# PIC32MZ.net
KiCad netlist of a schematic drawn in Altium Designer
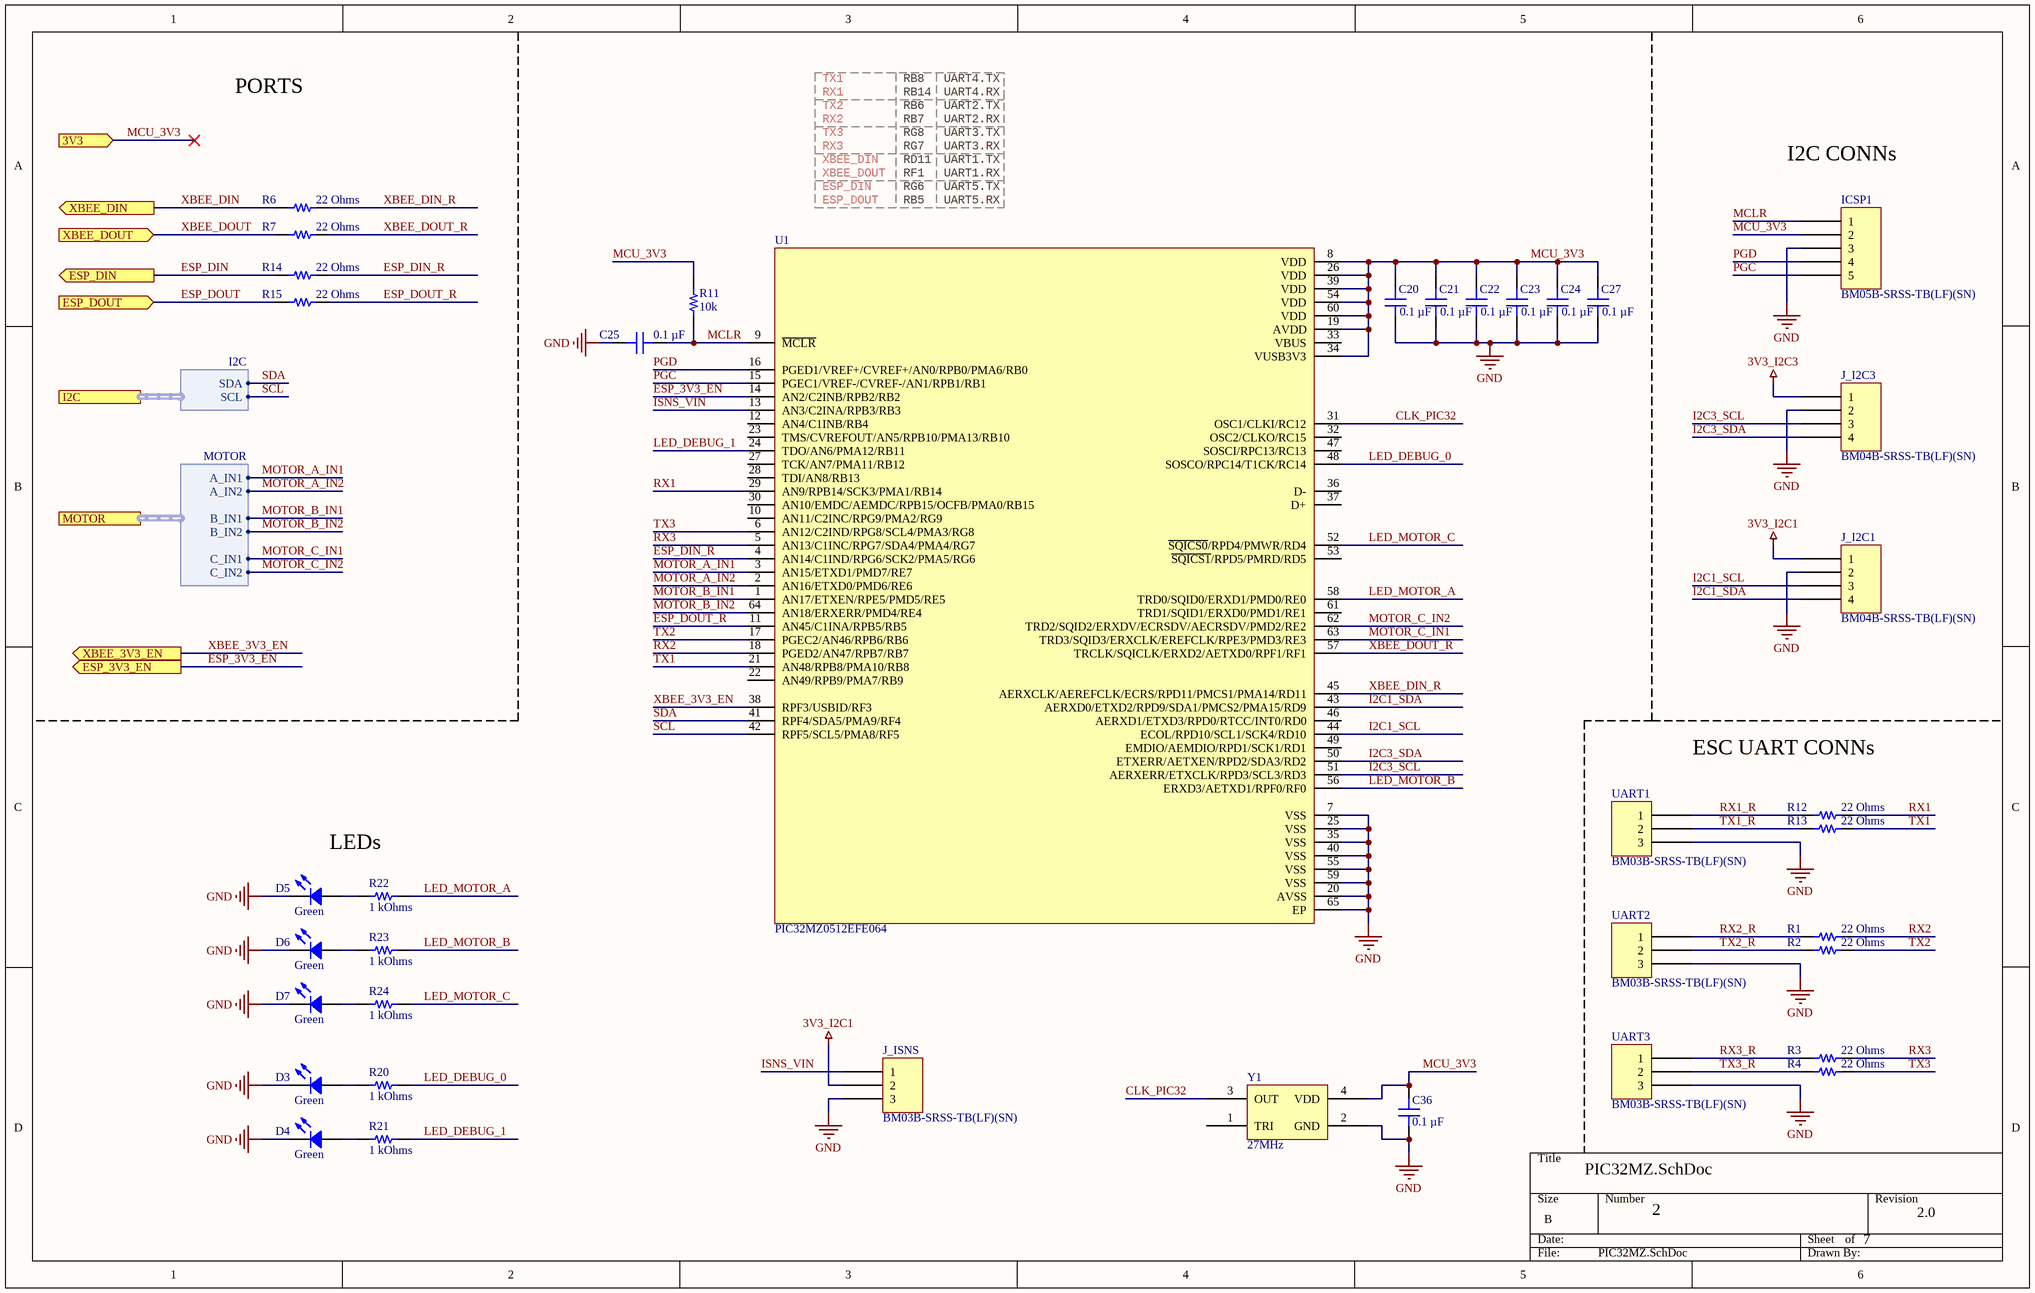
[diagram p0: PIC32MZ.SchDoc]

(export (version "E")
  (design (tool "Eeschema 10.0.6"))
  (components
    (comp (ref "C20")
      (value "0.1 µF")
      (footprint "CAP 0402_1005")
      (description "CAP CER 0.1UF 16V X7R 0402")
      (fields (field (name "PART NUMBER") "C0402C104K4RACAUTO") (field (name "MANUFACTURER") "KEMET"))
      (libsource (lib "Celestial Altium Library - altium_library") (part "Capacitor"))
    )
    (comp (ref "C21")
      (value "0.1 µF")
      (footprint "CAP 0402_1005")
      (description "CAP CER 0.1UF 16V X7R 0402")
      (fields (field (name "PART NUMBER") "C0402C104K4RACAUTO") (field (name "MANUFACTURER") "KEMET"))
      (libsource (lib "Celestial Altium Library - altium_library") (part "Capacitor"))
    )
    (comp (ref "C22")
      (value "0.1 µF")
      (footprint "CAP 0402_1005")
      (description "CAP CER 0.1UF 16V X7R 0402")
      (fields (field (name "PART NUMBER") "C0402C104K4RACAUTO") (field (name "MANUFACTURER") "KEMET"))
      (libsource (lib "Celestial Altium Library - altium_library") (part "Capacitor"))
    )
    (comp (ref "C23")
      (value "0.1 µF")
      (footprint "CAP 0402_1005")
      (description "CAP CER 0.1UF 16V X7R 0402")
      (fields (field (name "PART NUMBER") "C0402C104K4RACAUTO") (field (name "MANUFACTURER") "KEMET"))
      (libsource (lib "Celestial Altium Library - altium_library") (part "Capacitor"))
    )
    (comp (ref "C24")
      (value "0.1 µF")
      (footprint "CAP 0402_1005")
      (description "CAP CER 0.1UF 16V X7R 0402")
      (fields (field (name "PART NUMBER") "C0402C104K4RACAUTO") (field (name "MANUFACTURER") "KEMET"))
      (libsource (lib "Celestial Altium Library - altium_library") (part "Capacitor"))
    )
    (comp (ref "C25")
      (value "0.1 µF")
      (footprint "CAP 0402_1005")
      (description "CAP CER 0.1UF 16V X7R 0402")
      (fields (field (name "PART NUMBER") "C0402C104K4RACAUTO") (field (name "MANUFACTURER") "KEMET"))
      (libsource (lib "Celestial Altium Library - altium_library") (part "Capacitor"))
    )
    (comp (ref "C27")
      (value "0.1 µF")
      (footprint "CAP 0402_1005")
      (description "CAP CER 0.1UF 16V X7R 0402")
      (fields (field (name "PART NUMBER") "C0402C104K4RACAUTO") (field (name "MANUFACTURER") "KEMET"))
      (libsource (lib "Celestial Altium Library - altium_library") (part "Capacitor"))
    )
    (comp (ref "C36")
      (value "0.1 µF")
      (footprint "CAP 0402_1005")
      (description "CAP CER 0.1UF 16V X7R 0402")
      (fields (field (name "PART NUMBER") "C0402C104K4RACAUTO") (field (name "MANUFACTURER") "KEMET"))
      (libsource (lib "Celestial Altium Library - altium_library") (part "Capacitor"))
    )
    (comp (ref "D3")
      (value "Green")
      (footprint "LED 0603_1608 GREEN")
      (description "1.6X0.8MM LC GREEN PIXSOLED DOME")
      (fields (field (name "PART NUMBER") "XZCDGK53W-8VF") (field (name "MANUFACTURER") "SunLED"))
      (libsource (lib "Celestial Altium Library - altium_library") (part "LED"))
    )
    (comp (ref "D4")
      (value "Green")
      (footprint "LED 0603_1608 GREEN")
      (description "1.6X0.8MM LC GREEN PIXSOLED DOME")
      (fields (field (name "PART NUMBER") "XZCDGK53W-8VF") (field (name "MANUFACTURER") "SunLED"))
      (libsource (lib "Celestial Altium Library - altium_library") (part "LED"))
    )
    (comp (ref "D5")
      (value "Green")
      (footprint "LED 0603_1608 GREEN")
      (description "1.6X0.8MM LC GREEN PIXSOLED DOME")
      (fields (field (name "PART NUMBER") "XZCDGK53W-8VF") (field (name "MANUFACTURER") "SunLED"))
      (libsource (lib "Celestial Altium Library - altium_library") (part "LED"))
    )
    (comp (ref "D6")
      (value "Green")
      (footprint "LED 0603_1608 GREEN")
      (description "1.6X0.8MM LC GREEN PIXSOLED DOME")
      (fields (field (name "PART NUMBER") "XZCDGK53W-8VF") (field (name "MANUFACTURER") "SunLED"))
      (libsource (lib "Celestial Altium Library - altium_library") (part "LED"))
    )
    (comp (ref "D7")
      (value "Green")
      (footprint "LED 0603_1608 GREEN")
      (description "1.6X0.8MM LC GREEN PIXSOLED DOME")
      (fields (field (name "PART NUMBER") "XZCDGK53W-8VF") (field (name "MANUFACTURER") "SunLED"))
      (libsource (lib "Celestial Altium Library - altium_library") (part "LED"))
    )
    (comp (ref "ICSP1")
      (value "BM05B-SRSS-TB(LF)(SN)")
      (footprint "JST BM05B-SRSS-TB")
      (description "CONN HEADER SMD 5POS 1MM")
      (fields (field (name "MANUFACTURER") "JST Sales America Inc."))
      (libsource (lib "Celestial Altium Library - altium_library") (part "5 Pin"))
    )
    (comp (ref "J_I2C1")
      (value "BM04B-SRSS-TB(LF)(SN)")
      (footprint "JST BM04B-SRSS-TB")
      (description "CONN HEADER SMD 4POS 1MM")
      (fields (field (name "MANUFACTURER") "JST Sales America Inc."))
      (libsource (lib "Celestial Altium Library - altium_library") (part "4 Pin"))
    )
    (comp (ref "J_I2C3")
      (value "BM04B-SRSS-TB(LF)(SN)")
      (footprint "JST BM04B-SRSS-TB")
      (description "CONN HEADER SMD 4POS 1MM")
      (fields (field (name "MANUFACTURER") "JST Sales America Inc."))
      (libsource (lib "Celestial Altium Library - altium_library") (part "4 Pin"))
    )
    (comp (ref "J_ISNS")
      (value "BM03B-SRSS-TB(LF)(SN)")
      (footprint "JST BM03B-SRSS-TB")
      (description "CONN HEADER SMD 3POS 1MM")
      (fields (field (name "MANUFACTURER") "JST Sales America Inc."))
      (libsource (lib "") (part "3 Pin_1"))
    )
    (comp (ref "R1")
      (value "22 Ohms")
      (footprint "RES 0402_1005")
      (description "RES 14.3K OHM 1% 1/10W 0402")
      (fields
        (field (name "PART NUMBER") "RK73H1ETTP1432F")
        (field (name "MANUFACTURER") "KOA Speer Electronics, Inc.")
      )
      (libsource (lib "Celestial Altium Library - altium_library") (part "Resistor"))
    )
    (comp (ref "R2")
      (value "22 Ohms")
      (footprint "RES 0402_1005")
      (description "RES 14.3K OHM 1% 1/10W 0402")
      (fields
        (field (name "PART NUMBER") "RK73H1ETTP1432F")
        (field (name "MANUFACTURER") "KOA Speer Electronics, Inc.")
      )
      (libsource (lib "Celestial Altium Library - altium_library") (part "Resistor"))
    )
    (comp (ref "R3")
      (value "22 Ohms")
      (footprint "RES 0402_1005")
      (description "RES 14.3K OHM 1% 1/10W 0402")
      (fields
        (field (name "PART NUMBER") "RK73H1ETTP1432F")
        (field (name "MANUFACTURER") "KOA Speer Electronics, Inc.")
      )
      (libsource (lib "Celestial Altium Library - altium_library") (part "Resistor"))
    )
    (comp (ref "R4")
      (value "22 Ohms")
      (footprint "RES 0402_1005")
      (description "RES 14.3K OHM 1% 1/10W 0402")
      (fields
        (field (name "PART NUMBER") "RK73H1ETTP1432F")
        (field (name "MANUFACTURER") "KOA Speer Electronics, Inc.")
      )
      (libsource (lib "Celestial Altium Library - altium_library") (part "Resistor"))
    )
    (comp (ref "R6")
      (value "22 Ohms")
      (footprint "RES 0402_1005")
      (description "RES 14.3K OHM 1% 1/10W 0402")
      (fields
        (field (name "PART NUMBER") "RK73H1ETTP1432F")
        (field (name "MANUFACTURER") "KOA Speer Electronics, Inc.")
      )
      (libsource (lib "Celestial Altium Library - altium_library") (part "Resistor"))
    )
    (comp (ref "R7")
      (value "22 Ohms")
      (footprint "RES 0402_1005")
      (description "RES 14.3K OHM 1% 1/10W 0402")
      (fields
        (field (name "PART NUMBER") "RK73H1ETTP1432F")
        (field (name "MANUFACTURER") "KOA Speer Electronics, Inc.")
      )
      (libsource (lib "Celestial Altium Library - altium_library") (part "Resistor"))
    )
    (comp (ref "R11")
      (value "10k")
      (footprint "RES 0402_1005")
      (description "RES 14.3K OHM 1% 1/10W 0402")
      (fields
        (field (name "PART NUMBER") "RK73H1ETTP1432F")
        (field (name "MANUFACTURER") "KOA Speer Electronics, Inc.")
      )
      (libsource (lib "Celestial Altium Library - altium_library") (part "Resistor"))
    )
    (comp (ref "R12")
      (value "22 Ohms")
      (footprint "RES 0402_1005")
      (description "RES 14.3K OHM 1% 1/10W 0402")
      (fields
        (field (name "PART NUMBER") "RK73H1ETTP1432F")
        (field (name "MANUFACTURER") "KOA Speer Electronics, Inc.")
      )
      (libsource (lib "Celestial Altium Library - altium_library") (part "Resistor"))
    )
    (comp (ref "R13")
      (value "22 Ohms")
      (footprint "RES 0402_1005")
      (description "RES 14.3K OHM 1% 1/10W 0402")
      (fields
        (field (name "PART NUMBER") "RK73H1ETTP1432F")
        (field (name "MANUFACTURER") "KOA Speer Electronics, Inc.")
      )
      (libsource (lib "Celestial Altium Library - altium_library") (part "Resistor"))
    )
    (comp (ref "R14")
      (value "22 Ohms")
      (footprint "YAGEO RES 0402_1005")
      (description "RES 1K OHM 1% 1/16W 0402")
      (fields (field (name "PART NUMBER") "RC0402FR-071KL") (field (name "MANUFACTURER") "Yageo"))
      (libsource (lib "Celestial Altium Library - altium_library") (part "Resistor"))
    )
    (comp (ref "R15")
      (value "22 Ohms")
      (footprint "YAGEO RES 0402_1005")
      (description "RES 1K OHM 1% 1/16W 0402")
      (fields (field (name "PART NUMBER") "RC0402FR-071KL") (field (name "MANUFACTURER") "Yageo"))
      (libsource (lib "Celestial Altium Library - altium_library") (part "Resistor"))
    )
    (comp (ref "R20")
      (value "1 kOhms")
      (footprint "YAGEO RES 0402_1005")
      (description "RES 1K OHM 1% 1/16W 0402")
      (fields (field (name "PART NUMBER") "RC0402FR-071KL") (field (name "MANUFACTURER") "Yageo"))
      (libsource (lib "Celestial Altium Library - altium_library") (part "Resistor"))
    )
    (comp (ref "R21")
      (value "1 kOhms")
      (footprint "YAGEO RES 0402_1005")
      (description "RES 1K OHM 1% 1/16W 0402")
      (fields (field (name "PART NUMBER") "RC0402FR-071KL") (field (name "MANUFACTURER") "Yageo"))
      (libsource (lib "Celestial Altium Library - altium_library") (part "Resistor"))
    )
    (comp (ref "R22")
      (value "1 kOhms")
      (footprint "YAGEO RES 0402_1005")
      (description "RES 1K OHM 1% 1/16W 0402")
      (fields (field (name "PART NUMBER") "RC0402FR-071KL") (field (name "MANUFACTURER") "Yageo"))
      (libsource (lib "Celestial Altium Library - altium_library") (part "Resistor"))
    )
    (comp (ref "R23")
      (value "1 kOhms")
      (footprint "YAGEO RES 0402_1005")
      (description "RES 1K OHM 1% 1/16W 0402")
      (fields (field (name "PART NUMBER") "RC0402FR-071KL") (field (name "MANUFACTURER") "Yageo"))
      (libsource (lib "Celestial Altium Library - altium_library") (part "Resistor"))
    )
    (comp (ref "R24")
      (value "1 kOhms")
      (footprint "YAGEO RES 0402_1005")
      (description "RES 1K OHM 1% 1/16W 0402")
      (fields (field (name "PART NUMBER") "RC0402FR-071KL") (field (name "MANUFACTURER") "Yageo"))
      (libsource (lib "Celestial Altium Library - altium_library") (part "Resistor"))
    )
    (comp (ref "U1")
      (value "PIC32MZ0512EFE064")
      (footprint "QFN50P900X900X100-65N")
      (description "32-bit Microcontrollers - MCU 32-BIT MCU 512KB FL 128KB RAM, No Crypto")
      (fields (field (name "MF") "Microchip") (field (name "MP") "PIC32MZ2048EFG064T-I/PT"))
      (libsource (lib "IC") (part "PIC32MZ0512EFE064-I/PT"))
    )
    (comp (ref "UART1")
      (value "BM03B-SRSS-TB(LF)(SN)")
      (footprint "JST BM03B-SRSS-TB")
      (description "CONN HEADER SMD 3POS 1MM")
      (fields (field (name "MANUFACTURER") "JST Sales America Inc."))
      (libsource (lib "Celestial Altium Library - altium_library") (part "3 Pin"))
    )
    (comp (ref "UART2")
      (value "BM03B-SRSS-TB(LF)(SN)")
      (footprint "JST BM03B-SRSS-TB")
      (description "CONN HEADER SMD 3POS 1MM")
      (fields (field (name "MANUFACTURER") "JST Sales America Inc."))
      (libsource (lib "Celestial Altium Library - altium_library") (part "3 Pin"))
    )
    (comp (ref "UART3")
      (value "BM03B-SRSS-TB(LF)(SN)")
      (footprint "JST BM03B-SRSS-TB")
      (description "CONN HEADER SMD 3POS 1MM")
      (fields (field (name "MANUFACTURER") "JST Sales America Inc."))
      (libsource (lib "Celestial Altium Library - altium_library") (part "3 Pin"))
    )
    (comp (ref "Y1")
      (value "27MHz")
      (footprint "ABRACON ASD")
      (description "XTAL OSC XO 27.0000MHZ HCMOS SMD")
      (fields (field (name "PART NUMBER") "ASD3-27.000MHZ-EC-T") (field (name "MANUFACTURER") "Abracon LLC"))
      (libsource (lib "Celestial Altium Library - altium_library") (part "Abracon XO ASD"))
    )
  )
  (nets
    (net (code "3") (name "/CLK_PIC32") (class "Default")
      (node (ref "U1") (pin "31") (pinfunction "OSC1/CLKI/RC12_31") (pintype "passive"))
      (node (ref "Y1") (pin "3") (pinfunction "OUT_3") (pintype "passive"))
    )
    (net (code "4") (name "/ESP_3V3_EN") (class "Default")
      (node (ref "U1") (pin "14") (pinfunction "AN2/C2INB/RPB2/RB2_14") (pintype "passive"))
    )
    (net (code "5") (name "/ESP_DIN") (class "Default")
      (node (ref "R14") (pin "1") (pinfunction "1_1") (pintype "passive"))
    )
    (net (code "6") (name "/ESP_DIN_R") (class "Default")
      (node (ref "R14") (pin "2") (pinfunction "2_2") (pintype "passive"))
      (node (ref "U1") (pin "4") (pinfunction "AN14/C1IND/RPG6/SCK2/PMA5/RG6_4") (pintype "passive"))
    )
    (net (code "7") (name "/ESP_DOUT") (class "Default")
      (node (ref "R15") (pin "1") (pinfunction "1_1") (pintype "passive"))
    )
    (net (code "8") (name "/ESP_DOUT_R") (class "Default")
      (node (ref "R15") (pin "2") (pinfunction "2_2") (pintype "passive"))
      (node (ref "U1") (pin "11") (pinfunction "AN45/C1INA/RPB5/RB5_11") (pintype "passive"))
    )
    (net (code "9") (name "/I2C1_SCL") (class "Default")
      (node (ref "J_I2C1") (pin "3") (pinfunction "3_3") (pintype "passive"))
      (node (ref "U1") (pin "44") (pinfunction "ECOL/RPD10/SCL1/SCK4/RD10_44") (pintype "passive"))
    )
    (net (code "10") (name "/I2C1_SDA") (class "Default")
      (node (ref "J_I2C1") (pin "4") (pinfunction "4_4") (pintype "passive"))
      (node (ref "U1") (pin "43") (pinfunction "AERXD0/ETXD2/RPD9/SDA1/PMCS2/PMA15/RD9_43") (pintype "passive"))
    )
    (net (code "11") (name "/I2C3_SCL") (class "Default")
      (node (ref "J_I2C3") (pin "3") (pinfunction "3_3") (pintype "passive"))
      (node (ref "U1") (pin "51") (pinfunction "AERXERR/ETXCLK/RPD3/SCL3/RD3_51") (pintype "passive"))
    )
    (net (code "12") (name "/I2C3_SDA") (class "Default")
      (node (ref "J_I2C3") (pin "4") (pinfunction "4_4") (pintype "passive"))
      (node (ref "U1") (pin "50") (pinfunction "ETXERR/AETXEN/RPD2/SDA3/RD2_50") (pintype "passive"))
    )
    (net (code "13") (name "/ISNS_VIN") (class "Default")
      (node (ref "J_ISNS") (pin "1") (pinfunction "1_1") (pintype "passive"))
      (node (ref "U1") (pin "13") (pinfunction "AN3/C2INA/RPB3/RB3_13") (pintype "passive"))
    )
    (net (code "14") (name "/LED_DEBUG_0") (class "Default")
      (node (ref "R20") (pin "2") (pinfunction "2_2") (pintype "passive"))
      (node (ref "U1") (pin "48") (pinfunction "SOSCO/RPC14/T1CK/RC14_48") (pintype "passive"))
    )
    (net (code "15") (name "/LED_DEBUG_1") (class "Default")
      (node (ref "R21") (pin "2") (pinfunction "2_2") (pintype "passive"))
      (node (ref "U1") (pin "24") (pinfunction "TDO/AN6/PMA12/RB11_24") (pintype "passive"))
    )
    (net (code "16") (name "/LED_MOTOR_A") (class "Default")
      (node (ref "R22") (pin "2") (pinfunction "2_2") (pintype "passive"))
      (node (ref "U1") (pin "58") (pinfunction "TRD0/SQID0/ERXD1/PMD0/RE0_58") (pintype "passive"))
    )
    (net (code "17") (name "/LED_MOTOR_B") (class "Default")
      (node (ref "R23") (pin "2") (pinfunction "2_2") (pintype "passive"))
      (node (ref "U1") (pin "56") (pinfunction "ERXD3/AETXD1/RPF0/RF0_56") (pintype "passive"))
    )
    (net (code "18") (name "/LED_MOTOR_C") (class "Default")
      (node (ref "R24") (pin "2") (pinfunction "2_2") (pintype "passive"))
      (node (ref "U1") (pin "52") (pinfunction "~{SQICS0}/RPD4/PMWR/RD4_52") (pintype "passive"))
    )
    (net (code "19") (name "/MCLR") (class "Default")
      (node (ref "C25") (pin "1") (pinfunction "1_1") (pintype "passive"))
      (node (ref "ICSP1") (pin "1") (pinfunction "1_1") (pintype "passive"))
      (node (ref "R11") (pin "2") (pinfunction "2_2") (pintype "passive"))
      (node (ref "U1") (pin "9") (pinfunction "~{MCLR}_9") (pintype "passive"))
    )
    (net (code "20") (name "/MCU_3V3") (class "Default")
      (node (ref "C20") (pin "2") (pinfunction "2_2") (pintype "passive"))
      (node (ref "C21") (pin "2") (pinfunction "2_2") (pintype "passive"))
      (node (ref "C22") (pin "2") (pinfunction "2_2") (pintype "passive"))
      (node (ref "C23") (pin "2") (pinfunction "2_2") (pintype "passive"))
      (node (ref "C24") (pin "2") (pinfunction "2_2") (pintype "passive"))
      (node (ref "C27") (pin "2") (pinfunction "2_2") (pintype "passive"))
      (node (ref "C36") (pin "2") (pinfunction "2_2") (pintype "passive"))
      (node (ref "ICSP1") (pin "2") (pinfunction "2_2") (pintype "passive"))
      (node (ref "R11") (pin "1") (pinfunction "1_1") (pintype "passive"))
      (node (ref "U1") (pin "19") (pinfunction "AVDD_19") (pintype "passive"))
      (node (ref "U1") (pin "26") (pinfunction "VDD_26") (pintype "passive"))
      (node (ref "U1") (pin "34") (pinfunction "VUSB3V3_34") (pintype "passive"))
      (node (ref "U1") (pin "39") (pinfunction "VDD_39") (pintype "passive"))
      (node (ref "U1") (pin "54") (pinfunction "VDD_54") (pintype "passive"))
      (node (ref "U1") (pin "60") (pinfunction "VDD_60") (pintype "passive"))
      (node (ref "U1") (pin "8") (pinfunction "VDD_8") (pintype "passive"))
      (node (ref "Y1") (pin "4") (pinfunction "VDD_4") (pintype "passive"))
    )
    (net (code "21") (name "/MOTOR_A_IN1") (class "Default")
      (node (ref "U1") (pin "3") (pinfunction "AN15/ETXD1/PMD7/RE7_3") (pintype "passive"))
    )
    (net (code "22") (name "/MOTOR_A_IN2") (class "Default")
      (node (ref "U1") (pin "2") (pinfunction "AN16/ETXD0/PMD6/RE6_2") (pintype "passive"))
    )
    (net (code "23") (name "/MOTOR_B_IN1") (class "Default")
      (node (ref "U1") (pin "1") (pinfunction "AN17/ETXEN/RPE5/PMD5/RE5_1") (pintype "passive"))
    )
    (net (code "24") (name "/MOTOR_B_IN2") (class "Default")
      (node (ref "U1") (pin "64") (pinfunction "AN18/ERXERR/PMD4/RE4_64") (pintype "passive"))
    )
    (net (code "25") (name "/MOTOR_C_IN1") (class "Default")
      (node (ref "U1") (pin "63") (pinfunction "TRD3/SQID3/ERXCLK/EREFCLK/RPE3/PMD3/RE3_63") (pintype "passive"))
    )
    (net (code "26") (name "/MOTOR_C_IN2") (class "Default")
      (node (ref "U1") (pin "62") (pinfunction "TRD2/SQID2/ERXDV/ECRSDV/AECRSDV/PMD2/RE2_62") (pintype "passive"))
    )
    (net (code "27") (name "/PGC") (class "Default")
      (node (ref "ICSP1") (pin "5") (pinfunction "5_5") (pintype "passive"))
      (node (ref "U1") (pin "15") (pinfunction "PGEC1/VREF-/CVREF-/AN1/RPB1/RB1_15") (pintype "passive"))
    )
    (net (code "28") (name "/PGD") (class "Default")
      (node (ref "ICSP1") (pin "4") (pinfunction "4_4") (pintype "passive"))
      (node (ref "U1") (pin "16") (pinfunction "PGED1/VREF+/CVREF+/AN0/RPB0/PMA6/RB0_16") (pintype "passive"))
    )
    (net (code "29") (name "/RX1") (class "Default")
      (node (ref "R12") (pin "1") (pinfunction "1_1") (pintype "passive"))
      (node (ref "U1") (pin "29") (pinfunction "AN9/RPB14/SCK3/PMA1/RB14_29") (pintype "passive"))
    )
    (net (code "30") (name "/RX1_R") (class "Default")
      (node (ref "R12") (pin "2") (pinfunction "2_2") (pintype "passive"))
      (node (ref "UART1") (pin "1") (pinfunction "1_1") (pintype "passive"))
    )
    (net (code "31") (name "/RX2") (class "Default")
      (node (ref "R1") (pin "1") (pinfunction "1_1") (pintype "passive"))
      (node (ref "U1") (pin "18") (pinfunction "PGED2/AN47/RPB7/RB7_18") (pintype "passive"))
    )
    (net (code "32") (name "/RX2_R") (class "Default")
      (node (ref "R1") (pin "2") (pinfunction "2_2") (pintype "passive"))
      (node (ref "UART2") (pin "1") (pinfunction "1_1") (pintype "passive"))
    )
    (net (code "33") (name "/RX3") (class "Default")
      (node (ref "R3") (pin "1") (pinfunction "1_1") (pintype "passive"))
      (node (ref "U1") (pin "5") (pinfunction "AN13/C1INC/RPG7/SDA4/PMA4/RG7_5") (pintype "passive"))
    )
    (net (code "34") (name "/RX3_R") (class "Default")
      (node (ref "R3") (pin "2") (pinfunction "2_2") (pintype "passive"))
      (node (ref "UART3") (pin "1") (pinfunction "1_1") (pintype "passive"))
    )
    (net (code "35") (name "/SCL") (class "Default")
      (node (ref "U1") (pin "42") (pinfunction "RPF5/SCL5/PMA8/RF5_42") (pintype "passive"))
    )
    (net (code "36") (name "/SDA") (class "Default")
      (node (ref "U1") (pin "41") (pinfunction "RPF4/SDA5/PMA9/RF4_41") (pintype "passive"))
    )
    (net (code "37") (name "/TX1") (class "Default")
      (node (ref "R13") (pin "1") (pinfunction "1_1") (pintype "passive"))
      (node (ref "U1") (pin "21") (pinfunction "AN48/RPB8/PMA10/RB8_21") (pintype "passive"))
    )
    (net (code "38") (name "/TX1_R") (class "Default")
      (node (ref "R13") (pin "2") (pinfunction "2_2") (pintype "passive"))
      (node (ref "UART1") (pin "2") (pinfunction "2_2") (pintype "passive"))
    )
    (net (code "39") (name "/TX2") (class "Default")
      (node (ref "R2") (pin "1") (pinfunction "1_1") (pintype "passive"))
      (node (ref "U1") (pin "17") (pinfunction "PGEC2/AN46/RPB6/RB6_17") (pintype "passive"))
    )
    (net (code "40") (name "/TX2_R") (class "Default")
      (node (ref "R2") (pin "2") (pinfunction "2_2") (pintype "passive"))
      (node (ref "UART2") (pin "2") (pinfunction "2_2") (pintype "passive"))
    )
    (net (code "41") (name "/TX3") (class "Default")
      (node (ref "R4") (pin "1") (pinfunction "1_1") (pintype "passive"))
      (node (ref "U1") (pin "6") (pinfunction "AN12/C2IND/RPG8/SCL4/PMA3/RG8_6") (pintype "passive"))
    )
    (net (code "42") (name "/TX3_R") (class "Default")
      (node (ref "R4") (pin "2") (pinfunction "2_2") (pintype "passive"))
      (node (ref "UART3") (pin "2") (pinfunction "2_2") (pintype "passive"))
    )
    (net (code "43") (name "/XBEE_3V3_EN") (class "Default")
      (node (ref "U1") (pin "38") (pinfunction "RPF3/USBID/RF3_38") (pintype "passive"))
    )
    (net (code "44") (name "/XBEE_DIN") (class "Default")
      (node (ref "R6") (pin "2") (pinfunction "2_2") (pintype "passive"))
    )
    (net (code "45") (name "/XBEE_DIN_R") (class "Default")
      (node (ref "R6") (pin "1") (pinfunction "1_1") (pintype "passive"))
      (node (ref "U1") (pin "45") (pinfunction "AERXCLK/AEREFCLK/ECRS/RPD11/PMCS1/PMA14/RD11_45") (pintype "passive"))
    )
    (net (code "46") (name "/XBEE_DOUT") (class "Default")
      (node (ref "R7") (pin "2") (pinfunction "2_2") (pintype "passive"))
    )
    (net (code "47") (name "/XBEE_DOUT_R") (class "Default")
      (node (ref "R7") (pin "1") (pinfunction "1_1") (pintype "passive"))
      (node (ref "U1") (pin "57") (pinfunction "TRCLK/SQICLK/ERXD2/AETXD0/RPF1/RF1_57") (pintype "passive"))
    )
    (net (code "50") (name "3V3_I2C1") (class "Default")
      (node (ref "J_I2C1") (pin "1") (pinfunction "1_1") (pintype "passive"))
      (node (ref "J_ISNS") (pin "2") (pinfunction "2_2") (pintype "passive"))
    )
    (net (code "51") (name "3V3_I2C3") (class "Default")
      (node (ref "J_I2C3") (pin "1") (pinfunction "1_1") (pintype "passive"))
    )
    (net (code "52") (name "GND") (class "Default")
      (node (ref "C20") (pin "1") (pinfunction "1_1") (pintype "passive"))
      (node (ref "C21") (pin "1") (pinfunction "1_1") (pintype "passive"))
      (node (ref "C22") (pin "1") (pinfunction "1_1") (pintype "passive"))
      (node (ref "C23") (pin "1") (pinfunction "1_1") (pintype "passive"))
      (node (ref "C24") (pin "1") (pinfunction "1_1") (pintype "passive"))
      (node (ref "C25") (pin "2") (pinfunction "2_2") (pintype "passive"))
      (node (ref "C27") (pin "1") (pinfunction "1_1") (pintype "passive"))
      (node (ref "C36") (pin "1") (pinfunction "1_1") (pintype "passive"))
      (node (ref "D3") (pin "2") (pinfunction "2_2") (pintype "passive"))
      (node (ref "D4") (pin "2") (pinfunction "2_2") (pintype "passive"))
      (node (ref "D5") (pin "2") (pinfunction "2_2") (pintype "passive"))
      (node (ref "D6") (pin "2") (pinfunction "2_2") (pintype "passive"))
      (node (ref "D7") (pin "2") (pinfunction "2_2") (pintype "passive"))
      (node (ref "ICSP1") (pin "3") (pinfunction "3_3") (pintype "passive"))
      (node (ref "J_I2C1") (pin "2") (pinfunction "2_2") (pintype "passive"))
      (node (ref "J_I2C3") (pin "2") (pinfunction "2_2") (pintype "passive"))
      (node (ref "J_ISNS") (pin "3") (pinfunction "3_3") (pintype "passive"))
      (node (ref "U1") (pin "20") (pinfunction "AVSS_20") (pintype "passive"))
      (node (ref "U1") (pin "25") (pinfunction "VSS_25") (pintype "passive"))
      (node (ref "U1") (pin "35") (pinfunction "VSS_35") (pintype "passive"))
      (node (ref "U1") (pin "40") (pinfunction "VSS_40") (pintype "passive"))
      (node (ref "U1") (pin "55") (pinfunction "VSS_55") (pintype "passive"))
      (node (ref "U1") (pin "59") (pinfunction "VSS_59") (pintype "passive"))
      (node (ref "U1") (pin "65") (pinfunction "EP_65") (pintype "passive"))
      (node (ref "U1") (pin "7") (pinfunction "VSS_7") (pintype "passive"))
      (node (ref "UART1") (pin "3") (pinfunction "3_3") (pintype "passive"))
      (node (ref "UART2") (pin "3") (pinfunction "3_3") (pintype "passive"))
      (node (ref "UART3") (pin "3") (pinfunction "3_3") (pintype "passive"))
      (node (ref "Y1") (pin "2") (pinfunction "GND_2") (pintype "passive"))
    )
    (net (code "53") (name "Net-(D3-Pad1)") (class "Default")
      (node (ref "D3") (pin "1") (pinfunction "1_1") (pintype "passive"))
      (node (ref "R20") (pin "1") (pinfunction "1_1") (pintype "passive"))
    )
    (net (code "54") (name "Net-(D4-Pad1)") (class "Default")
      (node (ref "D4") (pin "1") (pinfunction "1_1") (pintype "passive"))
      (node (ref "R21") (pin "1") (pinfunction "1_1") (pintype "passive"))
    )
    (net (code "55") (name "Net-(D5-Pad1)") (class "Default")
      (node (ref "D5") (pin "1") (pinfunction "1_1") (pintype "passive"))
      (node (ref "R22") (pin "1") (pinfunction "1_1") (pintype "passive"))
    )
    (net (code "56") (name "Net-(D6-Pad1)") (class "Default")
      (node (ref "D6") (pin "1") (pinfunction "1_1") (pintype "passive"))
      (node (ref "R23") (pin "1") (pinfunction "1_1") (pintype "passive"))
    )
    (net (code "57") (name "Net-(D7-Pad1)") (class "Default")
      (node (ref "D7") (pin "1") (pinfunction "1_1") (pintype "passive"))
      (node (ref "R24") (pin "1") (pinfunction "1_1") (pintype "passive"))
    )
    (net (code "58") (name "unconnected-(U1-AERXD1{slash}ETXD3{slash}RPD0{slash}RTCC{slash}INT0{slash}RD0-Pad46)") (class "Default")
      (node (ref "U1") (pin "46") (pinfunction "AERXD1/ETXD3/RPD0/RTCC/INT0/RD0_46") (pintype "passive"))
    )
    (net (code "59") (name "unconnected-(U1-AN4{slash}C1INB{slash}RB4-Pad12)") (class "Default")
      (node (ref "U1") (pin "12") (pinfunction "AN4/C1INB/RB4_12") (pintype "passive"))
    )
    (net (code "60") (name "unconnected-(U1-AN10{slash}EMDC{slash}AEMDC{slash}RPB15{slash}OCFB{slash}PMA0{slash}RB15-Pad30)") (class "Default")
      (node (ref "U1") (pin "30") (pinfunction "AN10/EMDC/AEMDC/RPB15/OCFB/PMA0/RB15_30") (pintype "passive"))
    )
    (net (code "61") (name "unconnected-(U1-AN11{slash}C2INC{slash}RPG9{slash}PMA2{slash}RG9-Pad10)") (class "Default")
      (node (ref "U1") (pin "10") (pinfunction "AN11/C2INC/RPG9/PMA2/RG9_10") (pintype "passive"))
    )
    (net (code "62") (name "unconnected-(U1-AN49{slash}RPB9{slash}PMA7{slash}RB9-Pad22)") (class "Default")
      (node (ref "U1") (pin "22") (pinfunction "AN49/RPB9/PMA7/RB9_22") (pintype "passive"))
    )
    (net (code "63") (name "unconnected-(U1-D+-Pad37)") (class "Default")
      (node (ref "U1") (pin "37") (pinfunction "D+_37") (pintype "passive"))
    )
    (net (code "64") (name "unconnected-(U1-D--Pad36)") (class "Default")
      (node (ref "U1") (pin "36") (pinfunction "D-_36") (pintype "passive"))
    )
    (net (code "65") (name "unconnected-(U1-EMDIO{slash}AEMDIO{slash}RPD1{slash}SCK1{slash}RD1-Pad49)") (class "Default")
      (node (ref "U1") (pin "49") (pinfunction "EMDIO/AEMDIO/RPD1/SCK1/RD1_49") (pintype "passive"))
    )
    (net (code "66") (name "unconnected-(U1-OSC2{slash}CLKO{slash}RC15-Pad32)") (class "Default")
      (node (ref "U1") (pin "32") (pinfunction "OSC2/CLKO/RC15_32") (pintype "passive"))
    )
    (net (code "67") (name "unconnected-(U1-SOSCI{slash}RPC13{slash}RC13-Pad47)") (class "Default")
      (node (ref "U1") (pin "47") (pinfunction "SOSCI/RPC13/RC13_47") (pintype "passive"))
    )
    (net (code "68") (name "unconnected-(U1-TCK{slash}AN7{slash}PMA11{slash}RB12-Pad27)") (class "Default")
      (node (ref "U1") (pin "27") (pinfunction "TCK/AN7/PMA11/RB12_27") (pintype "passive"))
    )
    (net (code "69") (name "unconnected-(U1-TDI{slash}AN8{slash}RB13-Pad28)") (class "Default")
      (node (ref "U1") (pin "28") (pinfunction "TDI/AN8/RB13_28") (pintype "passive"))
    )
    (net (code "70") (name "unconnected-(U1-TMS{slash}CVREFOUT{slash}AN5{slash}RPB10{slash}PMA13{slash}RB10-Pad23)") (class "Default")
      (node (ref "U1") (pin "23") (pinfunction "TMS/CVREFOUT/AN5/RPB10/PMA13/RB10_23") (pintype "passive"))
    )
    (net (code "71") (name "unconnected-(U1-TRD1{slash}SQID1{slash}ERXD0{slash}PMD1{slash}RE1-Pad61)") (class "Default")
      (node (ref "U1") (pin "61") (pinfunction "TRD1/SQID1/ERXD0/PMD1/RE1_61") (pintype "passive"))
    )
    (net (code "72") (name "unconnected-(U1-VBUS-Pad33)") (class "Default")
      (node (ref "U1") (pin "33") (pinfunction "VBUS_33") (pintype "passive"))
    )
    (net (code "73") (name "unconnected-(U1-~{SQICS1}{slash}RPD5{slash}PMRD{slash}RD5-Pad53)") (class "Default")
      (node (ref "U1") (pin "53") (pinfunction "~{SQICS1}/RPD5/PMRD/RD5_53") (pintype "passive"))
    )
    (net (code "74") (name "unconnected-(Y1-TRI-Pad1)") (class "Default")
      (node (ref "Y1") (pin "1") (pinfunction "TRI_1") (pintype "passive"))
    )
  )
)
